# Power.net
KiCad netlist of a schematic drawn in Altium Designer
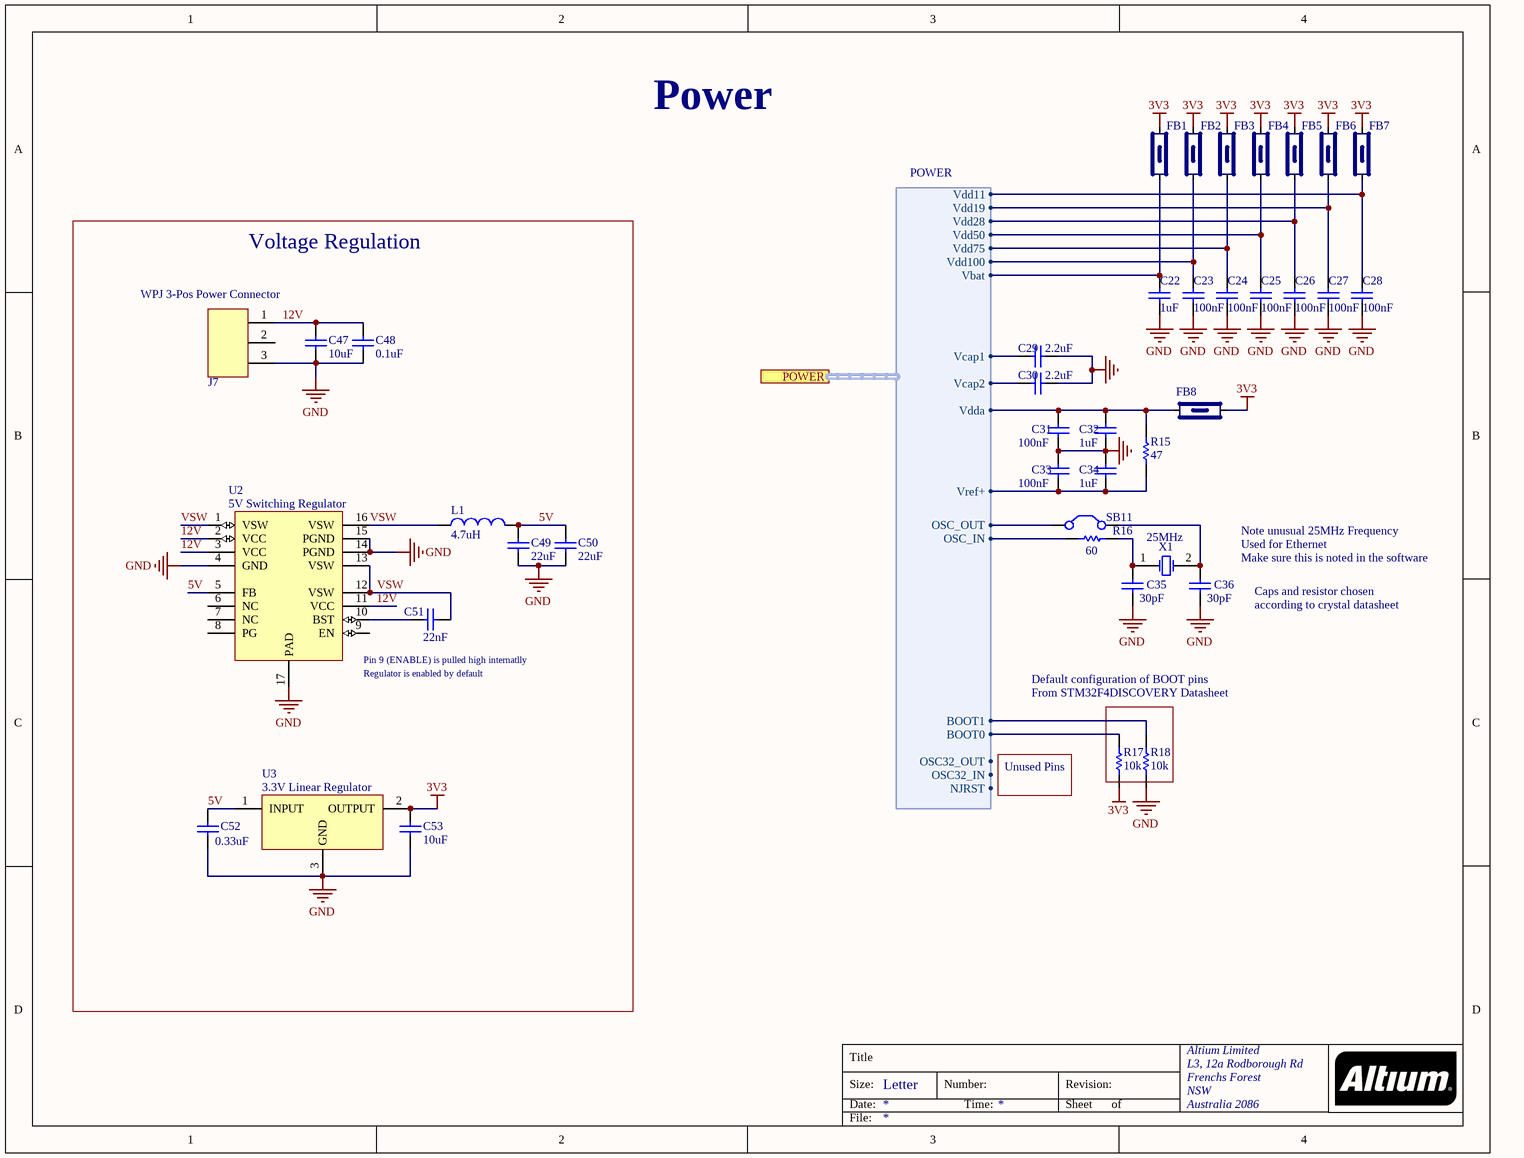
[diagram p0: Power.SchDoc]

(export (version "E")
  (design (tool "Eeschema 10.0.6"))
  (components
    (comp (ref "C22")
      (value "1uF")
      (footprint "0402")
      (description "Capacitor")
      (libsource (lib "Miscellaneous Devices") (part "Cap"))
    )
    (comp (ref "C23")
      (value "100nF")
      (footprint "0402")
      (description "Capacitor")
      (libsource (lib "Miscellaneous Devices") (part "Cap"))
    )
    (comp (ref "C24")
      (value "100nF")
      (footprint "0402")
      (description "Capacitor")
      (libsource (lib "Miscellaneous Devices") (part "Cap"))
    )
    (comp (ref "C25")
      (value "100nF")
      (footprint "0402")
      (description "Capacitor")
      (libsource (lib "Miscellaneous Devices") (part "Cap"))
    )
    (comp (ref "C26")
      (value "100nF")
      (footprint "0402")
      (description "Capacitor")
      (libsource (lib "Miscellaneous Devices") (part "Cap"))
    )
    (comp (ref "C27")
      (value "100nF")
      (footprint "0402")
      (description "Capacitor")
      (libsource (lib "Miscellaneous Devices") (part "Cap"))
    )
    (comp (ref "C28")
      (value "100nF")
      (footprint "0402")
      (description "Capacitor")
      (libsource (lib "Miscellaneous Devices") (part "Cap"))
    )
    (comp (ref "C29")
      (value "2.2uF")
      (footprint "0402")
      (description "Capacitor")
      (libsource (lib "Miscellaneous Devices") (part "Cap"))
    )
    (comp (ref "C30")
      (value "2.2uF")
      (footprint "0402")
      (description "Capacitor")
      (libsource (lib "Miscellaneous Devices") (part "Cap"))
    )
    (comp (ref "C31")
      (value "100nF")
      (footprint "0402")
      (description "Capacitor")
      (libsource (lib "Miscellaneous Devices") (part "Cap"))
    )
    (comp (ref "C32")
      (value "1uF")
      (footprint "0402")
      (description "Capacitor")
      (libsource (lib "Miscellaneous Devices") (part "Cap"))
    )
    (comp (ref "C33")
      (value "100nF")
      (footprint "0402")
      (description "Capacitor")
      (libsource (lib "Miscellaneous Devices") (part "Cap"))
    )
    (comp (ref "C34")
      (value "1uF")
      (footprint "0402")
      (description "Capacitor")
      (libsource (lib "Miscellaneous Devices") (part "Cap"))
    )
    (comp (ref "C35")
      (value "30pF")
      (footprint "0402")
      (description "Capacitor")
      (libsource (lib "Miscellaneous Devices") (part "Cap"))
    )
    (comp (ref "C36")
      (value "30pF")
      (footprint "0402")
      (description "Capacitor")
      (libsource (lib "Miscellaneous Devices") (part "Cap"))
    )
    (comp (ref "C47")
      (value "10uF")
      (footprint "0402")
      (description "Capacitor")
      (fields (field (name "Comment") "Cap") (field (name "PUBLISHER") "Altium Limited"))
      (libsource (lib "Miscellaneous Devices") (part "Cap"))
    )
    (comp (ref "C48")
      (value "0.1uF")
      (footprint "0402")
      (description "Capacitor")
      (fields (field (name "Comment") "Cap") (field (name "PUBLISHER") "Altium Limited"))
      (libsource (lib "Miscellaneous Devices") (part "Cap"))
    )
    (comp (ref "C49")
      (value "22uF")
      (footprint "0402")
      (description "Capacitor")
      (fields (field (name "Comment") "Cap"))
      (libsource (lib "Miscellaneous Devices") (part "Cap"))
    )
    (comp (ref "C50")
      (value "22uF")
      (footprint "0402")
      (description "Capacitor")
      (fields (field (name "Comment") "Cap"))
      (libsource (lib "Miscellaneous Devices") (part "Cap"))
    )
    (comp (ref "C51")
      (value "22nF")
      (footprint "0402")
      (description "Capacitor")
      (fields (field (name "Comment") "Cap"))
      (libsource (lib "Miscellaneous Devices") (part "Cap"))
    )
    (comp (ref "C52")
      (value "0.33uF")
      (footprint "0402")
      (description "Capacitor")
      (fields (field (name "Comment") "Cap"))
      (libsource (lib "Miscellaneous Devices") (part "Cap"))
    )
    (comp (ref "C53")
      (value "10uF")
      (footprint "0402")
      (description "Capacitor")
      (fields (field (name "Comment") "Cap"))
      (libsource (lib "Miscellaneous Devices") (part "Cap"))
    )
    (comp (ref "FB1")
      (value "Ferrite Bead")
      (footprint "0402")
      (libsource (lib "LaunchyRIOComponents") (part "Ferrite Bead"))
    )
    (comp (ref "FB2")
      (value "Ferrite Bead")
      (footprint "0402")
      (libsource (lib "LaunchyRIOComponents") (part "Ferrite Bead"))
    )
    (comp (ref "FB3")
      (value "Ferrite Bead")
      (footprint "0402")
      (libsource (lib "LaunchyRIOComponents") (part "Ferrite Bead"))
    )
    (comp (ref "FB4")
      (value "Ferrite Bead")
      (footprint "0402")
      (libsource (lib "LaunchyRIOComponents") (part "Ferrite Bead"))
    )
    (comp (ref "FB5")
      (value "Ferrite Bead")
      (footprint "0402")
      (libsource (lib "LaunchyRIOComponents") (part "Ferrite Bead"))
    )
    (comp (ref "FB6")
      (value "Ferrite Bead")
      (footprint "0402")
      (libsource (lib "LaunchyRIOComponents") (part "Ferrite Bead"))
    )
    (comp (ref "FB7")
      (value "Ferrite Bead")
      (footprint "0402")
      (libsource (lib "LaunchyRIOComponents") (part "Ferrite Bead"))
    )
    (comp (ref "FB8")
      (value "Ferrite Bead")
      (footprint "0402")
      (libsource (lib "LaunchyRIOComponents") (part "Ferrite Bead"))
    )
    (comp (ref "J7")
      (value "WPJ 3-Pos Power Connector")
      (footprint "WPJ-3Pos")
      (libsource (lib "LaunchyRIOComponents") (part "WPJ 3-Pos Power Connector"))
    )
    (comp (ref "L1")
      (value "4.7uH")
      (footprint "Inductor")
      (description "Inductor")
      (libsource (lib "Miscellaneous Devices") (part "Inductor"))
    )
    (comp (ref "R15")
      (value "47")
      (footprint "0402")
      (description "Resistor")
      (fields (field (name "Comment") "Res1"))
      (libsource (lib "Miscellaneous Devices") (part "Res1"))
    )
    (comp (ref "R16")
      (value "60")
      (footprint "0402")
      (description "Resistor")
      (fields (field (name "Comment") "Res1"))
      (libsource (lib "Miscellaneous Devices") (part "Res1"))
    )
    (comp (ref "R17")
      (value "10k")
      (footprint "0402")
      (description "Resistor")
      (fields (field (name "Comment") "Res1"))
      (libsource (lib "Miscellaneous Devices") (part "Res1"))
    )
    (comp (ref "R18")
      (value "10k")
      (footprint "0402")
      (description "Resistor")
      (fields (field (name "Comment") "Res1"))
      (libsource (lib "Miscellaneous Devices") (part "Res1"))
    )
    (comp (ref "SB11")
      (value "Jumper")
      (footprint "SB-2pos")
      (description "Jumper Wire")
      (libsource (lib "Miscellaneous Devices") (part "Jumper"))
    )
    (comp (ref "U2")
      (value "5V Switching Regulator")
      (footprint "VQFN16")
      (libsource (lib "LaunchyRIOComponents") (part "5V Switching Regulator"))
    )
    (comp (ref "U3")
      (value "3.3V Linear Regulator")
      (footprint "DPAK")
      (libsource (lib "LaunchyRIOComponents") (part "3.3V Linear Regulator"))
    )
    (comp (ref "X1")
      (value "XTAL")
      (footprint "4SMD 25MHZ CRYSTAL")
      (description "Crystal Oscillator")
      (fields
        (field (name "FREQUENCY") "25MHz")
        (field (name "DIGIKEY PART NUMBER") "FL2500316ZTR-ND")
        (field (name "MNF PART NO") "FL2500316Z")
      )
      (libsource (lib "Miscellaneous Devices") (part "XTAL"))
    )
  )
  (nets
    (net (code "2") (name "/5V") (class "Default")
      (node (ref "C49") (pin "1") (pinfunction "1_1") (pintype "passive"))
      (node (ref "C50") (pin "1") (pinfunction "1_1") (pintype "passive"))
      (node (ref "C52") (pin "1") (pinfunction "1_1") (pintype "passive"))
      (node (ref "L1") (pin "2") (pinfunction "2_2") (pintype "passive"))
      (node (ref "U2") (pin "5") (pinfunction "FB_5") (pintype "power_in"))
      (node (ref "U3") (pin "1") (pinfunction "INPUT_1") (pintype "power_in"))
    )
    (net (code "3") (name "/12V") (class "Default")
      (node (ref "C47") (pin "2") (pinfunction "2_2") (pintype "passive"))
      (node (ref "C48") (pin "2") (pinfunction "2_2") (pintype "passive"))
      (node (ref "J7") (pin "1") (pinfunction "1_1") (pintype "power_in"))
      (node (ref "U2") (pin "11") (pinfunction "VCC_11") (pintype "power_in"))
      (node (ref "U2") (pin "2") (pinfunction "VCC_2") (pintype "bidirectional"))
      (node (ref "U2") (pin "3") (pinfunction "VCC_3") (pintype "power_in"))
    )
    (net (code "4") (name "/BOOT0") (class "Default")
      (node (ref "R17") (pin "2") (pinfunction "2_2") (pintype "passive"))
    )
    (net (code "5") (name "/BOOT1") (class "Default")
      (node (ref "R18") (pin "2") (pinfunction "2_2") (pintype "passive"))
    )
    (net (code "6") (name "/OSC_IN") (class "Default")
      (node (ref "R16") (pin "2") (pinfunction "2_2") (pintype "passive"))
    )
    (net (code "7") (name "/OSC_OUT") (class "Default")
      (node (ref "SB11") (pin "1") (pinfunction "C1_1") (pintype "passive"))
    )
    (net (code "8") (name "/VSW") (class "Default")
      (node (ref "C51") (pin "1") (pinfunction "1_1") (pintype "passive"))
      (node (ref "L1") (pin "1") (pinfunction "1_1") (pintype "passive"))
      (node (ref "U2") (pin "1") (pinfunction "VSW_1") (pintype "bidirectional"))
      (node (ref "U2") (pin "12") (pinfunction "VSW_12") (pintype "power_in"))
      (node (ref "U2") (pin "13") (pinfunction "VSW_13") (pintype "power_in"))
      (node (ref "U2") (pin "16") (pinfunction "VSW_16") (pintype "power_in"))
    )
    (net (code "9") (name "/Vbat") (class "Default")
      (node (ref "C22") (pin "2") (pinfunction "2_2") (pintype "passive"))
      (node (ref "FB1") (pin "1") (pinfunction "1_1") (pintype "passive"))
    )
    (net (code "10") (name "/Vcap1") (class "Default")
      (node (ref "C29") (pin "2") (pinfunction "2_2") (pintype "passive"))
    )
    (net (code "11") (name "/Vcap2") (class "Default")
      (node (ref "C30") (pin "2") (pinfunction "2_2") (pintype "passive"))
    )
    (net (code "12") (name "/Vdd11") (class "Default")
      (node (ref "C28") (pin "2") (pinfunction "2_2") (pintype "passive"))
      (node (ref "FB7") (pin "1") (pinfunction "1_1") (pintype "passive"))
    )
    (net (code "13") (name "/Vdd19") (class "Default")
      (node (ref "C27") (pin "2") (pinfunction "2_2") (pintype "passive"))
      (node (ref "FB6") (pin "1") (pinfunction "1_1") (pintype "passive"))
    )
    (net (code "14") (name "/Vdd28") (class "Default")
      (node (ref "C26") (pin "2") (pinfunction "2_2") (pintype "passive"))
      (node (ref "FB5") (pin "1") (pinfunction "1_1") (pintype "passive"))
    )
    (net (code "15") (name "/Vdd50") (class "Default")
      (node (ref "C25") (pin "2") (pinfunction "2_2") (pintype "passive"))
      (node (ref "FB4") (pin "1") (pinfunction "1_1") (pintype "passive"))
    )
    (net (code "16") (name "/Vdd75") (class "Default")
      (node (ref "C24") (pin "2") (pinfunction "2_2") (pintype "passive"))
      (node (ref "FB3") (pin "1") (pinfunction "1_1") (pintype "passive"))
    )
    (net (code "17") (name "/Vdd100") (class "Default")
      (node (ref "C23") (pin "2") (pinfunction "2_2") (pintype "passive"))
      (node (ref "FB2") (pin "1") (pinfunction "1_1") (pintype "passive"))
    )
    (net (code "18") (name "/Vdda") (class "Default")
      (node (ref "C31") (pin "2") (pinfunction "2_2") (pintype "passive"))
      (node (ref "C32") (pin "2") (pinfunction "2_2") (pintype "passive"))
      (node (ref "FB8") (pin "1") (pinfunction "1_1") (pintype "passive"))
      (node (ref "R15") (pin "2") (pinfunction "2_2") (pintype "passive"))
    )
    (net (code "19") (name "/Vref+") (class "Default")
      (node (ref "C33") (pin "1") (pinfunction "1_1") (pintype "passive"))
      (node (ref "C34") (pin "1") (pinfunction "1_1") (pintype "passive"))
      (node (ref "R15") (pin "1") (pinfunction "1_1") (pintype "passive"))
    )
    (net (code "21") (name "3V3") (class "Default")
      (node (ref "C53") (pin "1") (pinfunction "1_1") (pintype "passive"))
      (node (ref "FB1") (pin "2") (pinfunction "2_2") (pintype "passive"))
      (node (ref "FB2") (pin "2") (pinfunction "2_2") (pintype "passive"))
      (node (ref "FB3") (pin "2") (pinfunction "2_2") (pintype "passive"))
      (node (ref "FB4") (pin "2") (pinfunction "2_2") (pintype "passive"))
      (node (ref "FB5") (pin "2") (pinfunction "2_2") (pintype "passive"))
      (node (ref "FB6") (pin "2") (pinfunction "2_2") (pintype "passive"))
      (node (ref "FB7") (pin "2") (pinfunction "2_2") (pintype "passive"))
      (node (ref "FB8") (pin "2") (pinfunction "2_2") (pintype "passive"))
      (node (ref "R17") (pin "1") (pinfunction "1_1") (pintype "passive"))
      (node (ref "U3") (pin "2") (pinfunction "OUTPUT_2") (pintype "power_in"))
    )
    (net (code "22") (name "GND") (class "Default")
      (node (ref "C22") (pin "1") (pinfunction "1_1") (pintype "passive"))
      (node (ref "C23") (pin "1") (pinfunction "1_1") (pintype "passive"))
      (node (ref "C24") (pin "1") (pinfunction "1_1") (pintype "passive"))
      (node (ref "C25") (pin "1") (pinfunction "1_1") (pintype "passive"))
      (node (ref "C26") (pin "1") (pinfunction "1_1") (pintype "passive"))
      (node (ref "C27") (pin "1") (pinfunction "1_1") (pintype "passive"))
      (node (ref "C28") (pin "1") (pinfunction "1_1") (pintype "passive"))
      (node (ref "C29") (pin "1") (pinfunction "1_1") (pintype "passive"))
      (node (ref "C30") (pin "1") (pinfunction "1_1") (pintype "passive"))
      (node (ref "C31") (pin "1") (pinfunction "1_1") (pintype "passive"))
      (node (ref "C32") (pin "1") (pinfunction "1_1") (pintype "passive"))
      (node (ref "C33") (pin "2") (pinfunction "2_2") (pintype "passive"))
      (node (ref "C34") (pin "2") (pinfunction "2_2") (pintype "passive"))
      (node (ref "C35") (pin "1") (pinfunction "1_1") (pintype "passive"))
      (node (ref "C36") (pin "1") (pinfunction "1_1") (pintype "passive"))
      (node (ref "C47") (pin "1") (pinfunction "1_1") (pintype "passive"))
      (node (ref "C48") (pin "1") (pinfunction "1_1") (pintype "passive"))
      (node (ref "C49") (pin "2") (pinfunction "2_2") (pintype "passive"))
      (node (ref "C50") (pin "2") (pinfunction "2_2") (pintype "passive"))
      (node (ref "C52") (pin "2") (pinfunction "2_2") (pintype "passive"))
      (node (ref "C53") (pin "2") (pinfunction "2_2") (pintype "passive"))
      (node (ref "J7") (pin "3") (pinfunction "3_3") (pintype "power_in"))
      (node (ref "R18") (pin "1") (pinfunction "1_1") (pintype "passive"))
      (node (ref "U2") (pin "14") (pinfunction "PGND_14") (pintype "power_in"))
      (node (ref "U2") (pin "15") (pinfunction "PGND_15") (pintype "power_in"))
      (node (ref "U2") (pin "17") (pinfunction "PAD_17") (pintype "power_in"))
      (node (ref "U2") (pin "4") (pinfunction "GND_4") (pintype "power_in"))
      (node (ref "U3") (pin "3") (pinfunction "GND_3") (pintype "power_in"))
    )
    (net (code "23") (name "Net-(SB11-C2)") (class "Default")
      (node (ref "C36") (pin "2") (pinfunction "2_2") (pintype "passive"))
      (node (ref "SB11") (pin "2") (pinfunction "C2_2") (pintype "passive"))
      (node (ref "X1") (pin "2") (pinfunction "OSC2_2") (pintype "passive"))
    )
    (net (code "24") (name "Net-(U2-BST)") (class "Default")
      (node (ref "C51") (pin "2") (pinfunction "2_2") (pintype "passive"))
      (node (ref "U2") (pin "10") (pinfunction "BST_10") (pintype "bidirectional"))
    )
    (net (code "25") (name "Net-(X1-OSC1)") (class "Default")
      (node (ref "C35") (pin "2") (pinfunction "2_2") (pintype "passive"))
      (node (ref "R16") (pin "1") (pinfunction "1_1") (pintype "passive"))
      (node (ref "X1") (pin "1") (pinfunction "OSC1_1") (pintype "passive"))
    )
    (net (code "26") (name "unconnected-(J7-Pad2)") (class "Default")
      (node (ref "J7") (pin "2") (pinfunction "2_2") (pintype "power_in"))
    )
    (net (code "27") (name "unconnected-(U2-EN-Pad9)") (class "Default")
      (node (ref "U2") (pin "9") (pinfunction "EN_9") (pintype "bidirectional"))
    )
    (net (code "28") (name "unconnected-(U2-NC-Pad6)") (class "Default")
      (node (ref "U2") (pin "6") (pinfunction "NC_6") (pintype "power_in"))
    )
    (net (code "29") (name "unconnected-(U2-NC-Pad7)") (class "Default")
      (node (ref "U2") (pin "7") (pinfunction "NC_7") (pintype "power_in"))
    )
    (net (code "30") (name "unconnected-(U2-PG-Pad8)") (class "Default")
      (node (ref "U2") (pin "8") (pinfunction "PG_8") (pintype "power_in"))
    )
  )
)
